# 006_EEPR_DISCHAR.net
KiCad netlist of a schematic drawn in Altium Designer
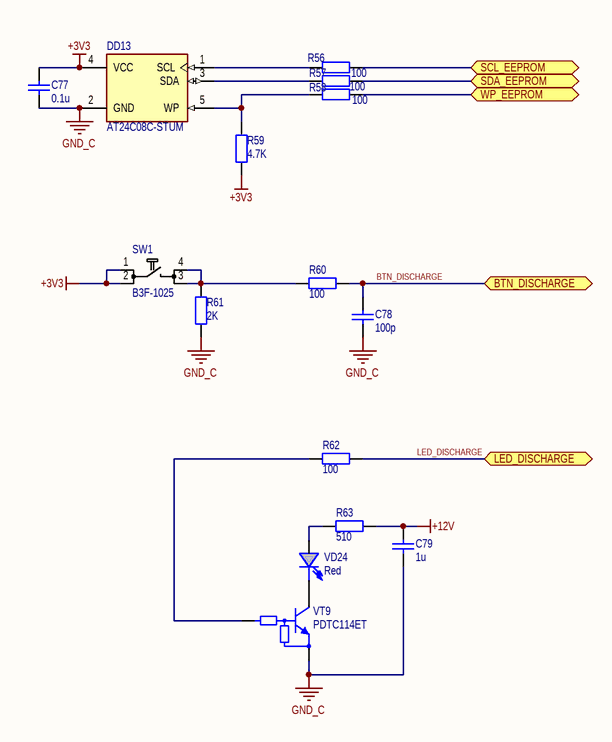
[diagram p0: 006_EEPR_DISCHAR.SchDoc]

(export (version "E")
  (design (tool "Eeschema 10.0.6"))
  (components
    (comp (ref "C77")
      (value "0.1u")
      (footprint "mainLib:SMD_C_0603")
      (description "SMD C 0603 MURATA 50V 10% X7R")
      (fields (field (name "PARTNUMBER") "GRM188R71H104K") (field (name "MANUFACTURER") "MURATA"))
      (libsource (lib "mainRCLib") (part "C0603 0.1u 50V 10%"))
    )
    (comp (ref "C78")
      (value "100p")
      (footprint "mainLib:SMD_C_0603")
      (description "SMD C 0603 MURATA 100V 5% NP0")
      (fields (field (name "PARTNUMBER") "GRM1885C2A101JA01") (field (name "MANUFACTURER") "MURATA"))
      (libsource (lib "mainRCLib") (part "C0603 100p 100V 5%"))
    )
    (comp (ref "C79")
      (value "1u")
      (footprint "mainLib:SMD_C_0603")
      (description "SMD C 0603 MURATA 25V 10% X7R")
      (fields (field (name "PARTNUMBER") "GRM188R71E105KA12") (field (name "MANUFACTURER") "MURATA"))
      (libsource (lib "mainRCLib") (part "C0603 1uF 25V 10%"))
    )
    (comp (ref "DD13")
      (value "AT24C08C-STUM")
      (footprint "mainLib:5TS1")
      (description "I2C Serial EEPROM, 8-Kbit (1024 x 8)")
      (fields (field (name "PARTNUMBER") "AT24C08C-STUM-T") (field (name "MANUFACTURER") "ATMEL"))
      (libsource (lib "mainLib") (part "AT24C08C-STUM"))
    )
    (comp (ref "R56")
      (value "100")
      (footprint "SMD_R_0603")
      (description "SMD R 0603 VISHAY 0.1W 75V 1% 100ppm")
      (fields (field (name "PARTNUMBER") "CRCW0603100RFK") (field (name "MANUFACTURER") "VISHAY"))
      (libsource (lib "mainRCLib") (part "R0603 100 1%"))
    )
    (comp (ref "R57")
      (value "100")
      (footprint "SMD_R_0603")
      (description "SMD R 0603 VISHAY 0.1W 75V 1% 100ppm")
      (fields (field (name "PARTNUMBER") "CRCW0603100RFK") (field (name "MANUFACTURER") "VISHAY"))
      (libsource (lib "mainRCLib") (part "R0603 100 1%"))
    )
    (comp (ref "R58")
      (value "100")
      (footprint "SMD_R_0603")
      (description "SMD R 0603 VISHAY 0.1W 75V 1% 100ppm")
      (fields (field (name "PARTNUMBER") "CRCW0603100RFK") (field (name "MANUFACTURER") "VISHAY"))
      (libsource (lib "mainRCLib") (part "R0603 100 1%"))
    )
    (comp (ref "R59")
      (value "4.7K")
      (footprint "mainLib:SMD_R_0805")
      (description "SMD R 0805 VISHAY 0.125W 150V 1% 100ppm")
      (fields (field (name "PARTNUMBER") "CRCW08054K70FK") (field (name "MANUFACTURER") "VISHAY"))
      (libsource (lib "mainRCLib") (part "R0805 4.7K 1%"))
    )
    (comp (ref "R60")
      (value "100")
      (footprint "SMD_R_0603")
      (description "SMD R 0603 VISHAY 0.1W 75V 1% 100ppm")
      (fields (field (name "PARTNUMBER") "CRCW0603100RFK") (field (name "MANUFACTURER") "VISHAY"))
      (libsource (lib "mainRCLib") (part "R0603 100 1%"))
    )
    (comp (ref "R61")
      (value "2K")
      (footprint "mainLib:SMD_R_0805")
      (description "SMD R 0805 VISHAY 0.125W 150V 1% 100ppm")
      (fields (field (name "PARTNUMBER") "CRCW08052K00FK") (field (name "MANUFACTURER") "VISHAY"))
      (libsource (lib "mainRCLib") (part "R0805 2K 1%"))
    )
    (comp (ref "R62")
      (value "100")
      (footprint "SMD_R_0603")
      (description "SMD R 0603 VISHAY 0.1W 75V 1% 100ppm")
      (fields (field (name "PARTNUMBER") "CRCW0603100RFK") (field (name "MANUFACTURER") "VISHAY"))
      (libsource (lib "mainRCLib") (part "R0603 100 1%"))
    )
    (comp (ref "R63")
      (value "510")
      (footprint "mainLib:SMD_R_1206")
      (description "SMD R 1206 VISHAY 0.25W 200V 1% 100ppm")
      (fields (field (name "PARTNUMBER") "CRCW1206510RFK") (field (name "MANUFACTURER") "VISHAY"))
      (libsource (lib "mainRCLib") (part "R1206 510 1%"))
    )
    (comp (ref "SW1")
      (value "B3F-1025")
      (footprint "mainLib:B3F-1025 (no gnd)")
      (description "1-50mA; 5-24V; 6x6mm h=5mm; Red")
      (fields (field (name "MANUFACTURER") "Omron"))
      (libsource (lib "mainLib") (part "B3F-1025"))
    )
    (comp (ref "VD24")
      (value "Red")
      (footprint "mainLib:SMD_LED_LL_Red")
      (description "LED Red SMD")
      (fields (field (name "PARTNUMBER") "LL-S172SC-2S") (field (name "MANUFACTURER") "Lucky Light"))
      (libsource (lib "mainLib") (part "LL-S172SC-2S"))
    )
    (comp (ref "VT9")
      (value "PDTC114ET")
      (footprint "mainLib:SOT23-3")
      (description "Digital Transistor (BRT), R1=10 kOhm, R2=10 kOhm, NPN Transistor")
      (fields (field (name "MANUFACTURER") "On Semiconductor"))
      (libsource (lib "mainLib") (part "PDTC114ET"))
    )
  )
  (nets
    (net (code "1") (name "+3V3") (class "Default")
      (node (ref "C77") (pin "2") (pinfunction "2_2") (pintype "passive"))
      (node (ref "DD13") (pin "4") (pinfunction "VCC_4") (pintype "power_in"))
      (node (ref "R59") (pin "1") (pinfunction "1_1") (pintype "passive"))
      (node (ref "SW1") (pin "1") (pinfunction "1_1") (pintype "passive"))
      (node (ref "SW1") (pin "2") (pinfunction "2_2") (pintype "passive"))
    )
    (net (code "2") (name "+12V") (class "Default")
      (node (ref "C79") (pin "2") (pinfunction "2_2") (pintype "passive"))
      (node (ref "R63") (pin "2") (pinfunction "2_2") (pintype "passive"))
    )
    (net (code "3") (name "/BTN_DISCHARGE") (class "Default")
      (node (ref "C78") (pin "2") (pinfunction "2_2") (pintype "passive"))
      (node (ref "R60") (pin "2") (pinfunction "2_2") (pintype "passive"))
    )
    (net (code "4") (name "/LED_DISCHARGE") (class "Default")
      (node (ref "R62") (pin "2") (pinfunction "2_2") (pintype "passive"))
    )
    (net (code "5") (name "/SCL_EEPROM") (class "Default")
      (node (ref "R56") (pin "2") (pinfunction "2_2") (pintype "passive"))
    )
    (net (code "6") (name "/SDA_EEPROM") (class "Default")
      (node (ref "R57") (pin "2") (pinfunction "2_2") (pintype "passive"))
    )
    (net (code "7") (name "/WP_EEPROM") (class "Default")
      (node (ref "R58") (pin "2") (pinfunction "2_2") (pintype "passive"))
    )
    (net (code "8") (name "GND_C") (class "Default")
      (node (ref "C77") (pin "1") (pinfunction "1_1") (pintype "passive"))
      (node (ref "C78") (pin "1") (pinfunction "1_1") (pintype "passive"))
      (node (ref "C79") (pin "1") (pinfunction "1_1") (pintype "passive"))
      (node (ref "DD13") (pin "2") (pinfunction "GND_2") (pintype "power_in"))
      (node (ref "R61") (pin "1") (pinfunction "1_1") (pintype "passive"))
      (node (ref "VT9") (pin "2") (pinfunction "E_2") (pintype "passive"))
    )
    (net (code "9") (name "Net-(DD13-SCL)") (class "Default")
      (node (ref "DD13") (pin "1") (pinfunction "SCL_1") (pintype "input"))
      (node (ref "R56") (pin "1") (pinfunction "1_1") (pintype "passive"))
    )
    (net (code "10") (name "Net-(DD13-SDA)") (class "Default")
      (node (ref "DD13") (pin "3") (pinfunction "SDA_3") (pintype "bidirectional"))
      (node (ref "R57") (pin "1") (pinfunction "1_1") (pintype "passive"))
    )
    (net (code "11") (name "Net-(DD13-WP)") (class "Default")
      (node (ref "DD13") (pin "5") (pinfunction "WP_5") (pintype "input"))
      (node (ref "R58") (pin "1") (pinfunction "1_1") (pintype "passive"))
      (node (ref "R59") (pin "2") (pinfunction "2_2") (pintype "passive"))
    )
    (net (code "12") (name "Net-(R60-Pad1)") (class "Default")
      (node (ref "R60") (pin "1") (pinfunction "1_1") (pintype "passive"))
      (node (ref "R61") (pin "2") (pinfunction "2_2") (pintype "passive"))
      (node (ref "SW1") (pin "3") (pinfunction "3_3") (pintype "passive"))
      (node (ref "SW1") (pin "4") (pinfunction "4_4") (pintype "passive"))
    )
    (net (code "13") (name "Net-(VD24-ANODE)") (class "Default")
      (node (ref "R63") (pin "1") (pinfunction "1_1") (pintype "passive"))
      (node (ref "VD24") (pin "1") (pinfunction "ANODE_1") (pintype "passive"))
    )
    (net (code "14") (name "Net-(VD24-CATHODE)") (class "Default")
      (node (ref "VD24") (pin "2") (pinfunction "CATHODE_2") (pintype "passive"))
      (node (ref "VT9") (pin "3") (pinfunction "C_3") (pintype "passive"))
    )
    (net (code "15") (name "Net-(VT9-B)") (class "Default")
      (node (ref "R62") (pin "1") (pinfunction "1_1") (pintype "passive"))
      (node (ref "VT9") (pin "1") (pinfunction "B_1") (pintype "passive"))
    )
  )
)
